# design.net
KiCad netlist of a schematic drawn in Altium Designer
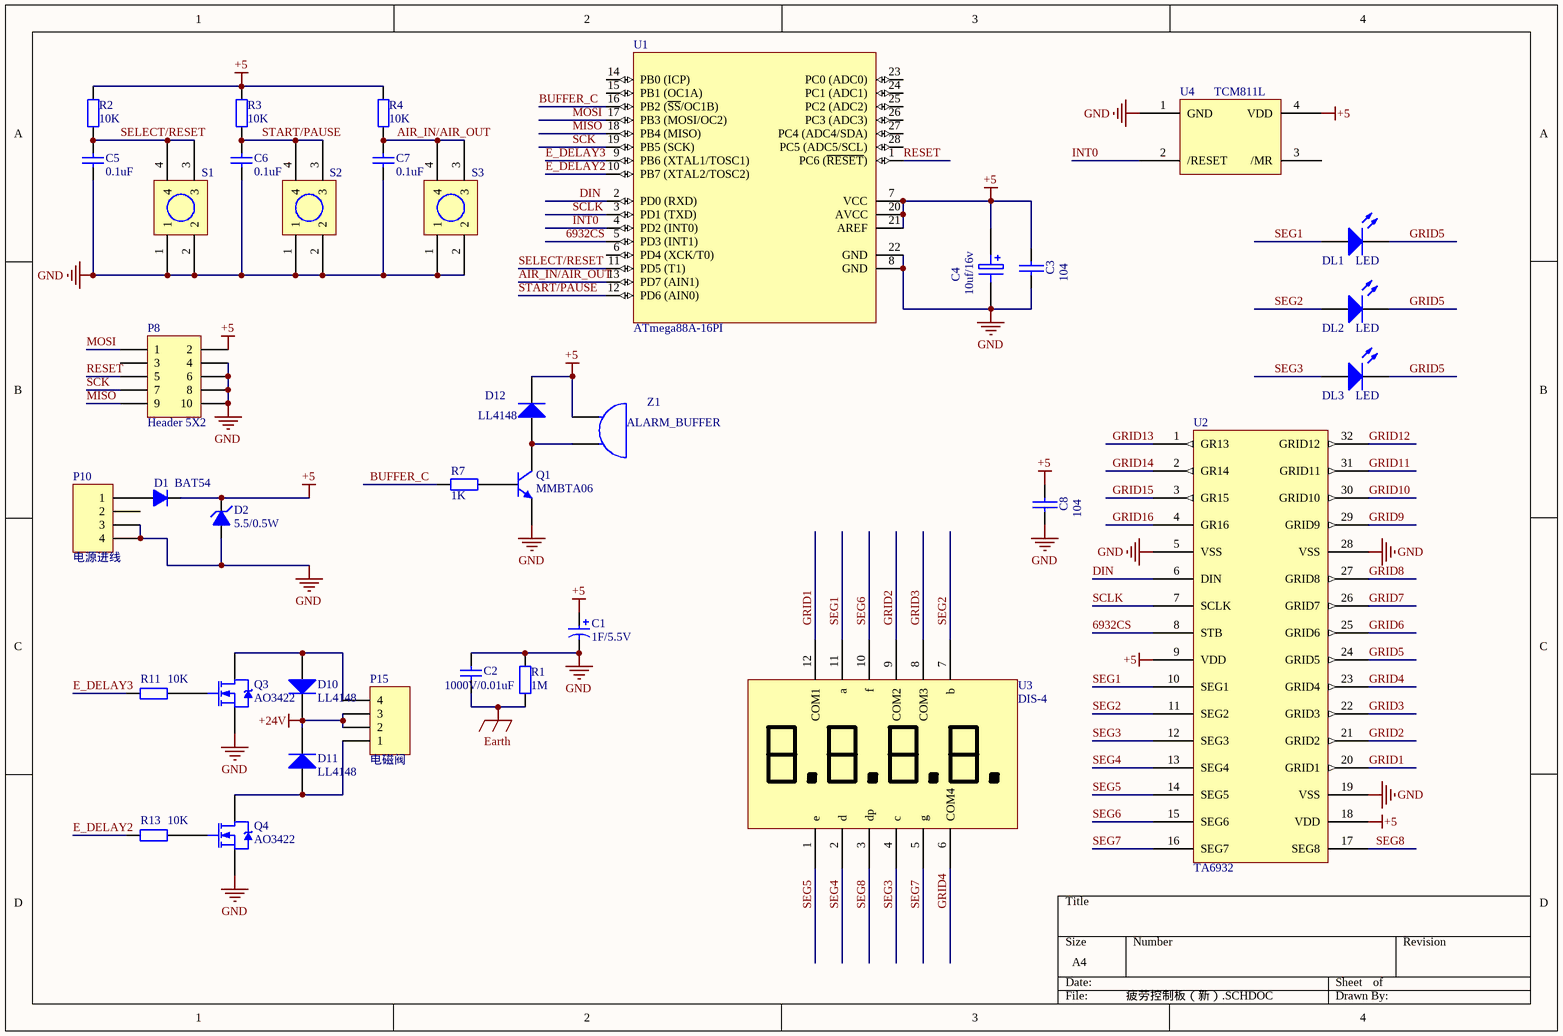
[diagram p0: 疲劳控制板（新）.SCHDOC]

(export (version "E")
  (design (tool "Eeschema 10.0.6"))
  (components
    (comp (ref "C1") (value "1F/5.5V") (footprint "法拉电容") (libsource (lib "自定义元件2") (part "电解电容")))
    (comp (ref "C2")
      (value "1000V/0.01uF")
      (footprint "0805")
      (description "Capacitor")
      (fields (field (name "Comment") "Cap") (field (name "PUBLISHER") "Altium Limited"))
      (libsource (lib "Miscellaneous Devices") (part "Cap"))
    )
    (comp (ref "C3")
      (value "104")
      (footprint "0805")
      (description "Capacitor")
      (libsource (lib "*") (part "CAP"))
    )
    (comp (ref "C4")
      (value "10uf/16v")
      (footprint "贴片极性电容(小)")
      (description "Electrolytic Capacitor")
      (libsource (lib "*") (part "ELECTRO1"))
    )
    (comp (ref "C5")
      (value "0.1uF")
      (footprint "0805")
      (description "Capacitor")
      (fields (field (name "Comment") "Cap") (field (name "PUBLISHER") "Altium Limited"))
      (libsource (lib "Miscellaneous Devices") (part "Cap"))
    )
    (comp (ref "C6")
      (value "0.1uF")
      (footprint "0805")
      (description "Capacitor")
      (fields (field (name "Comment") "Cap") (field (name "PUBLISHER") "Altium Limited"))
      (libsource (lib "Miscellaneous Devices") (part "Cap"))
    )
    (comp (ref "C7")
      (value "0.1uF")
      (footprint "0805")
      (description "Capacitor")
      (fields (field (name "Comment") "Cap") (field (name "PUBLISHER") "Altium Limited"))
      (libsource (lib "Miscellaneous Devices") (part "Cap"))
    )
    (comp (ref "C8")
      (value "104")
      (footprint "0805")
      (description "Capacitor")
      (libsource (lib "*") (part "CAP"))
    )
    (comp (ref "D1") (value "BAT54") (footprint "SOT-23") (libsource (lib "自定义元件2") (part "二极管")))
    (comp (ref "D2")
      (value "5.5/0.5W")
      (footprint "MELF-D3516-1406")
      (description "稳压二极管")
      (libsource (lib "自定义元件2") (part "稳压二极管"))
    )
    (comp (ref "D10")
      (value "LL4148")
      (footprint "MELF-D3516-1406")
      (description "Default Diode")
      (fields (field (name "PUBLISHER") "Altium Limited"))
      (libsource (lib "Miscellaneous Devices") (part "Diode"))
    )
    (comp (ref "D11")
      (value "LL4148")
      (footprint "MELF-D3516-1406")
      (description "Default Diode")
      (fields (field (name "PUBLISHER") "Altium Limited"))
      (libsource (lib "Miscellaneous Devices") (part "Diode"))
    )
    (comp (ref "D12")
      (value "LL4148")
      (footprint "MELF-D3516-1406")
      (description "Default Diode")
      (fields (field (name "PUBLISHER") "Altium Limited"))
      (libsource (lib "Miscellaneous Devices") (part "Diode"))
    )
    (comp (ref "DL1")
      (value "LED")
      (footprint "LED1")
      (description "发光二极管")
      (libsource (lib "自定义元件") (part "LED"))
    )
    (comp (ref "DL2")
      (value "LED")
      (footprint "LED1")
      (description "发光二极管")
      (libsource (lib "自定义元件") (part "LED"))
    )
    (comp (ref "DL3")
      (value "LED")
      (footprint "LED1")
      (description "发光二极管")
      (libsource (lib "自定义元件") (part "LED"))
    )
    (comp (ref "P8")
      (value "Header 5X2")
      (footprint "HDR2X5")
      (description "Header, 5-Pin, Dual row")
      (fields (field (name "PUBLISHER") "Altium Limited"))
      (libsource (lib "Miscellaneous Connectors") (part "Header 5X2"))
    )
    (comp (ref "P10")
      (value "电源进线")
      (footprint "免螺丝接线端子1")
      (description "Header, 4-Pin")
      (fields (field (name "PUBLISHER") "Altium Limited"))
      (libsource (lib "Miscellaneous Connectors") (part "MHDR1X4"))
    )
    (comp (ref "P15")
      (value "电磁阀")
      (footprint "免螺丝接线端子1")
      (description "Header, 4-Pin")
      (fields (field (name "PUBLISHER") "Altium Limited"))
      (libsource (lib "") (part "MHDR1X4_1"))
    )
    (comp (ref "Q1")
      (value "MMBTA06")
      (footprint "三极管_SOT23")
      (libsource (lib "自定义元件") (part "NPN三极管-SOT23"))
    )
    (comp (ref "Q3")
      (value "AO3422")
      (footprint "SOT-23")
      (description "N沟道功率MOSFET")
      (fields (field (name "PUBLISHER") "Altium Limited"))
      (libsource (lib "IR Discrete MOSFET - Power") (part "IRF530"))
    )
    (comp (ref "Q4")
      (value "AO3422")
      (footprint "SOT-23")
      (description "N沟道功率MOSFET")
      (fields (field (name "PUBLISHER") "Altium Limited"))
      (libsource (lib "IR Discrete MOSFET - Power") (part "IRF530"))
    )
    (comp (ref "R1")
      (value "1M")
      (footprint "0805")
      (description "Resistor")
      (fields (field (name "Comment") "Res2") (field (name "PUBLISHER") "Altium Limited"))
      (libsource (lib "") (part "Res2_1"))
    )
    (comp (ref "R2")
      (value "10K")
      (footprint "0805")
      (description "贴片电阻")
      (libsource (lib "") (part "Res2_1"))
    )
    (comp (ref "R3")
      (value "10K")
      (footprint "0805")
      (description "Resistor")
      (libsource (lib "") (part "Res2_1"))
    )
    (comp (ref "R4")
      (value "10K")
      (footprint "0805")
      (description "Resistor")
      (libsource (lib "") (part "Res2_1"))
    )
    (comp (ref "R7")
      (value "1K")
      (footprint "0805")
      (description "Resistor")
      (libsource (lib "Miscellaneous Devices") (part "Res2"))
    )
    (comp (ref "R11")
      (value "10K")
      (footprint "0805")
      (description "贴片电阻")
      (fields (field (name "PUBLISHER") "Altium Limited"))
      (libsource (lib "Miscellaneous Devices") (part "Res2"))
    )
    (comp (ref "R13")
      (value "10K")
      (footprint "0805")
      (description "贴片电阻")
      (fields (field (name "PUBLISHER") "Altium Limited"))
      (libsource (lib "Miscellaneous Devices") (part "Res2"))
    )
    (comp (ref "S1")
      (value "~")
      (footprint "AN-NIU")
      (description "S?")
      (libsource (lib "*") (part "ANJIAN"))
    )
    (comp (ref "S2")
      (value "~")
      (footprint "AN-NIU")
      (description "S?")
      (libsource (lib "*") (part "ANJIAN"))
    )
    (comp (ref "S3")
      (value "~")
      (footprint "AN-NIU")
      (description "S?")
      (libsource (lib "*") (part "ANJIAN"))
    )
    (comp (ref "U1")
      (value "ATmega88A-16PI")
      (footprint "DIP28(300mil)")
      (description "8-Bit AVR Microcontroller with 8K Bytes of In-System Programmable Flash Memory")
      (fields (field (name "PUBLISHER") "Altium Limited"))
      (libsource (lib "Atmel Microcontroller 8-Bit AVR") (part "ATmega8-16PI"))
    )
    (comp (ref "U2") (value "TA6932") (footprint "TM6932") (libsource (lib "*") (part "TM6932")))
    (comp (ref "U3") (value "DIS-4") (footprint "DIS05_4") (libsource (lib "*") (part "DIS-4")))
    (comp (ref "U4") (value "TCM811L") (footprint "SOT-143") (libsource (lib "*") (part "TCM811")))
    (comp (ref "Z1")
      (value "ALARM_BUFFER")
      (footprint "BUFFER")
      (description "Buzzer")
      (libsource (lib "*") (part "BUZZER"))
    )
  )
  (nets
    (net (code "1") (name "+5") (class "Default")
      (node (ref "C1") (pin "1") (pinfunction "1_1") (pintype "passive"))
      (node (ref "C3") (pin "1") (pinfunction "1_1") (pintype "passive"))
      (node (ref "C4") (pin "1") (pinfunction "1_1") (pintype "passive"))
      (node (ref "C8") (pin "1") (pinfunction "1_1") (pintype "passive"))
      (node (ref "D1") (pin "3") (pinfunction "3_3") (pintype "passive"))
      (node (ref "D12") (pin "2") (pinfunction "K_2") (pintype "passive"))
      (node (ref "D2") (pin "2") (pinfunction "2_2") (pintype "passive"))
      (node (ref "P8") (pin "2") (pinfunction "2_2") (pintype "passive"))
      (node (ref "R2") (pin "2") (pinfunction "2_2") (pintype "passive"))
      (node (ref "R3") (pin "2") (pinfunction "2_2") (pintype "passive"))
      (node (ref "R4") (pin "2") (pinfunction "2_2") (pintype "passive"))
      (node (ref "U1") (pin "20") (pinfunction "AVCC_20") (pintype "power_in"))
      (node (ref "U1") (pin "21") (pinfunction "AREF_21") (pintype "passive"))
      (node (ref "U1") (pin "7") (pinfunction "VCC_7") (pintype "power_in"))
      (node (ref "U2") (pin "18") (pinfunction "VDD_18") (pintype "passive"))
      (node (ref "U2") (pin "9") (pinfunction "VDD_9") (pintype "passive"))
      (node (ref "U4") (pin "4") (pinfunction "VDD_4") (pintype "power_in"))
      (node (ref "Z1") (pin "1") (pinfunction "A_1") (pintype "passive"))
    )
    (net (code "2") (name "+24V") (class "Default")
      (node (ref "D10") (pin "2") (pinfunction "K_2") (pintype "passive"))
      (node (ref "D11") (pin "2") (pinfunction "K_2") (pintype "passive"))
      (node (ref "P15") (pin "2") (pinfunction "2_2") (pintype "passive"))
      (node (ref "P15") (pin "3") (pinfunction "3_3") (pintype "passive"))
    )
    (net (code "3") (name "/6932CS") (class "Default")
      (node (ref "U1") (pin "5") (pinfunction "PD3_(INT1)_5") (pintype "bidirectional"))
      (node (ref "U2") (pin "8") (pinfunction "STB_8") (pintype "passive"))
    )
    (net (code "4") (name "/AIR_IN{slash}AIR_OUT") (class "Default")
      (node (ref "C7") (pin "2") (pinfunction "2_2") (pintype "passive"))
      (node (ref "R4") (pin "1") (pinfunction "1_1") (pintype "passive"))
      (node (ref "S3") (pin "3") (pinfunction "3_3") (pintype "passive"))
      (node (ref "S3") (pin "4") (pinfunction "4_4") (pintype "passive"))
      (node (ref "U1") (pin "13") (pinfunction "PD7_(AIN1)_13") (pintype "bidirectional"))
    )
    (net (code "5") (name "/BUFFER_C") (class "Default")
      (node (ref "R7") (pin "2") (pinfunction "2_2") (pintype "passive"))
      (node (ref "U1") (pin "16") (pinfunction "PB2_(~{SS}/OC1B)_16") (pintype "bidirectional"))
    )
    (net (code "6") (name "/DIN") (class "Default")
      (node (ref "U1") (pin "2") (pinfunction "PD0_(RXD)_2") (pintype "bidirectional"))
      (node (ref "U2") (pin "6") (pinfunction "DIN_6") (pintype "passive"))
    )
    (net (code "7") (name "/E_DELAY2") (class "Default")
      (node (ref "R13") (pin "2") (pinfunction "2_2") (pintype "passive"))
      (node (ref "U1") (pin "10") (pinfunction "PB7_(XTAL2/TOSC2)_10") (pintype "bidirectional"))
    )
    (net (code "8") (name "/E_DELAY3") (class "Default")
      (node (ref "R11") (pin "2") (pinfunction "2_2") (pintype "passive"))
      (node (ref "U1") (pin "9") (pinfunction "PB6_(XTAL1/TOSC1)_9") (pintype "bidirectional"))
    )
    (net (code "9") (name "/GRID1") (class "Default")
      (node (ref "U2") (pin "20") (pinfunction "GRID1_20") (pintype "output"))
      (node (ref "U3") (pin "12") (pinfunction "COM1_12") (pintype "passive"))
    )
    (net (code "10") (name "/GRID2") (class "Default")
      (node (ref "U2") (pin "21") (pinfunction "GRID2_21") (pintype "output"))
      (node (ref "U3") (pin "9") (pinfunction "COM2_9") (pintype "passive"))
    )
    (net (code "11") (name "/GRID3") (class "Default")
      (node (ref "U2") (pin "22") (pinfunction "GRID3_22") (pintype "output"))
      (node (ref "U3") (pin "8") (pinfunction "COM3_8") (pintype "passive"))
    )
    (net (code "12") (name "/GRID4") (class "Default")
      (node (ref "U2") (pin "23") (pinfunction "GRID4_23") (pintype "output"))
      (node (ref "U3") (pin "6") (pinfunction "COM4_6") (pintype "passive"))
    )
    (net (code "13") (name "/GRID5") (class "Default")
      (node (ref "DL1") (pin "2") (pinfunction "K_2") (pintype "passive"))
      (node (ref "DL2") (pin "2") (pinfunction "K_2") (pintype "passive"))
      (node (ref "DL3") (pin "2") (pinfunction "K_2") (pintype "passive"))
      (node (ref "U2") (pin "24") (pinfunction "GRID5_24") (pintype "output"))
    )
    (net (code "14") (name "/GRID6") (class "Default")
      (node (ref "U2") (pin "25") (pinfunction "GRID6_25") (pintype "output"))
    )
    (net (code "15") (name "/GRID7") (class "Default")
      (node (ref "U2") (pin "26") (pinfunction "GRID7_26") (pintype "output"))
    )
    (net (code "16") (name "/GRID8") (class "Default")
      (node (ref "U2") (pin "27") (pinfunction "GRID8_27") (pintype "output"))
    )
    (net (code "17") (name "/GRID9") (class "Default")
      (node (ref "U2") (pin "29") (pinfunction "GRID9_29") (pintype "output"))
    )
    (net (code "18") (name "/GRID10") (class "Default")
      (node (ref "U2") (pin "30") (pinfunction "GRID10_30") (pintype "output"))
    )
    (net (code "19") (name "/GRID11") (class "Default")
      (node (ref "U2") (pin "31") (pinfunction "GRID11_31") (pintype "output"))
    )
    (net (code "20") (name "/GRID12") (class "Default")
      (node (ref "U2") (pin "32") (pinfunction "GRID12_32") (pintype "output"))
    )
    (net (code "21") (name "/GRID13") (class "Default")
      (node (ref "U2") (pin "1") (pinfunction "GR13_1") (pintype "output"))
    )
    (net (code "22") (name "/GRID14") (class "Default")
      (node (ref "U2") (pin "2") (pinfunction "GR14_2") (pintype "output"))
    )
    (net (code "23") (name "/GRID15") (class "Default")
      (node (ref "U2") (pin "3") (pinfunction "GR15_3") (pintype "output"))
    )
    (net (code "24") (name "/GRID16") (class "Default")
      (node (ref "U2") (pin "4") (pinfunction "GR16_4") (pintype "passive"))
    )
    (net (code "25") (name "/INT0") (class "Default")
      (node (ref "U1") (pin "4") (pinfunction "PD2_(INT0)_4") (pintype "bidirectional"))
      (node (ref "U4") (pin "2") (pinfunction "/RESET_2") (pintype "power_in"))
    )
    (net (code "26") (name "/MISO") (class "Default")
      (node (ref "P8") (pin "9") (pinfunction "9_9") (pintype "passive"))
      (node (ref "U1") (pin "18") (pinfunction "PB4_(MISO)_18") (pintype "bidirectional"))
    )
    (net (code "27") (name "/MOSI") (class "Default")
      (node (ref "P8") (pin "1") (pinfunction "1_1") (pintype "passive"))
      (node (ref "U1") (pin "17") (pinfunction "PB3_(MOSI/OC2)_17") (pintype "bidirectional"))
    )
    (net (code "28") (name "/RESET") (class "Default")
      (node (ref "P8") (pin "5") (pinfunction "5_5") (pintype "passive"))
      (node (ref "U1") (pin "1") (pinfunction "PC6_(~{RESET})_1") (pintype "bidirectional"))
    )
    (net (code "29") (name "/SCK") (class "Default")
      (node (ref "P8") (pin "7") (pinfunction "7_7") (pintype "passive"))
      (node (ref "U1") (pin "19") (pinfunction "PB5_(SCK)_19") (pintype "bidirectional"))
    )
    (net (code "30") (name "/SCLK") (class "Default")
      (node (ref "U1") (pin "3") (pinfunction "PD1_(TXD)_3") (pintype "bidirectional"))
      (node (ref "U2") (pin "7") (pinfunction "SCLK_7") (pintype "passive"))
    )
    (net (code "31") (name "/SEG1") (class "Default")
      (node (ref "DL1") (pin "1") (pinfunction "A_1") (pintype "passive"))
      (node (ref "U2") (pin "10") (pinfunction "SEG1_10") (pintype "passive"))
      (node (ref "U3") (pin "11") (pinfunction "a_11") (pintype "passive"))
    )
    (net (code "32") (name "/SEG2") (class "Default")
      (node (ref "DL2") (pin "1") (pinfunction "A_1") (pintype "passive"))
      (node (ref "U2") (pin "11") (pinfunction "SEG2_11") (pintype "passive"))
      (node (ref "U3") (pin "7") (pinfunction "b_7") (pintype "passive"))
    )
    (net (code "33") (name "/SEG3") (class "Default")
      (node (ref "DL3") (pin "1") (pinfunction "A_1") (pintype "passive"))
      (node (ref "U2") (pin "12") (pinfunction "SEG3_12") (pintype "passive"))
      (node (ref "U3") (pin "4") (pinfunction "c_4") (pintype "passive"))
    )
    (net (code "34") (name "/SEG4") (class "Default")
      (node (ref "U2") (pin "13") (pinfunction "SEG4_13") (pintype "passive"))
      (node (ref "U3") (pin "2") (pinfunction "d_2") (pintype "passive"))
    )
    (net (code "35") (name "/SEG5") (class "Default")
      (node (ref "U2") (pin "14") (pinfunction "SEG5_14") (pintype "passive"))
      (node (ref "U3") (pin "1") (pinfunction "e_1") (pintype "passive"))
    )
    (net (code "36") (name "/SEG6") (class "Default")
      (node (ref "U2") (pin "15") (pinfunction "SEG6_15") (pintype "passive"))
      (node (ref "U3") (pin "10") (pinfunction "f_10") (pintype "passive"))
    )
    (net (code "37") (name "/SEG7") (class "Default")
      (node (ref "U2") (pin "16") (pinfunction "SEG7_16") (pintype "passive"))
      (node (ref "U3") (pin "5") (pinfunction "g_5") (pintype "passive"))
    )
    (net (code "38") (name "/SEG8") (class "Default")
      (node (ref "U2") (pin "17") (pinfunction "SEG8_17") (pintype "passive"))
      (node (ref "U3") (pin "3") (pinfunction "dp_3") (pintype "passive"))
    )
    (net (code "39") (name "/SELECT{slash}RESET") (class "Default")
      (node (ref "C5") (pin "2") (pinfunction "2_2") (pintype "passive"))
      (node (ref "R2") (pin "1") (pinfunction "1_1") (pintype "passive"))
      (node (ref "S1") (pin "3") (pinfunction "3_3") (pintype "passive"))
      (node (ref "S1") (pin "4") (pinfunction "4_4") (pintype "passive"))
      (node (ref "U1") (pin "11") (pinfunction "PD5_(T1)_11") (pintype "bidirectional"))
    )
    (net (code "40") (name "/START{slash}PAUSE") (class "Default")
      (node (ref "C6") (pin "2") (pinfunction "2_2") (pintype "passive"))
      (node (ref "R3") (pin "1") (pinfunction "1_1") (pintype "passive"))
      (node (ref "S2") (pin "3") (pinfunction "3_3") (pintype "passive"))
      (node (ref "S2") (pin "4") (pinfunction "4_4") (pintype "passive"))
      (node (ref "U1") (pin "12") (pinfunction "PD6_(AIN0)_12") (pintype "bidirectional"))
    )
    (net (code "41") (name "Earth") (class "Default")
      (node (ref "C2") (pin "1") (pinfunction "1_1") (pintype "passive"))
      (node (ref "R1") (pin "1") (pinfunction "1_1") (pintype "passive"))
    )
    (net (code "42") (name "GND") (class "Default")
      (node (ref "C1") (pin "2") (pinfunction "2_2") (pintype "passive"))
      (node (ref "C2") (pin "2") (pinfunction "2_2") (pintype "passive"))
      (node (ref "C3") (pin "2") (pinfunction "2_2") (pintype "passive"))
      (node (ref "C4") (pin "2") (pinfunction "2_2") (pintype "passive"))
      (node (ref "C5") (pin "1") (pinfunction "1_1") (pintype "passive"))
      (node (ref "C6") (pin "1") (pinfunction "1_1") (pintype "passive"))
      (node (ref "C7") (pin "1") (pinfunction "1_1") (pintype "passive"))
      (node (ref "C8") (pin "2") (pinfunction "2_2") (pintype "passive"))
      (node (ref "D2") (pin "1") (pinfunction "1_1") (pintype "passive"))
      (node (ref "P10") (pin "3") (pinfunction "3_3") (pintype "passive"))
      (node (ref "P10") (pin "4") (pinfunction "4_4") (pintype "passive"))
      (node (ref "P8") (pin "10") (pinfunction "10_10") (pintype "passive"))
      (node (ref "P8") (pin "4") (pinfunction "4_4") (pintype "passive"))
      (node (ref "P8") (pin "6") (pinfunction "6_6") (pintype "passive"))
      (node (ref "P8") (pin "8") (pinfunction "8_8") (pintype "passive"))
      (node (ref "Q1") (pin "E") (pinfunction "E_E") (pintype "passive"))
      (node (ref "Q3") (pin "3") (pinfunction "S_3") (pintype "passive"))
      (node (ref "Q4") (pin "3") (pinfunction "S_3") (pintype "passive"))
      (node (ref "R1") (pin "2") (pinfunction "2_2") (pintype "passive"))
      (node (ref "S1") (pin "1") (pinfunction "1_1") (pintype "passive"))
      (node (ref "S1") (pin "2") (pinfunction "2_2") (pintype "passive"))
      (node (ref "S2") (pin "1") (pinfunction "1_1") (pintype "passive"))
      (node (ref "S2") (pin "2") (pinfunction "2_2") (pintype "passive"))
      (node (ref "S3") (pin "1") (pinfunction "1_1") (pintype "passive"))
      (node (ref "S3") (pin "2") (pinfunction "2_2") (pintype "passive"))
      (node (ref "U1") (pin "22") (pinfunction "GND_22") (pintype "power_in"))
      (node (ref "U1") (pin "8") (pinfunction "GND_8") (pintype "power_in"))
      (node (ref "U2") (pin "19") (pinfunction "VSS_19") (pintype "passive"))
      (node (ref "U2") (pin "28") (pinfunction "VSS_28") (pintype "passive"))
      (node (ref "U2") (pin "5") (pinfunction "VSS_5") (pintype "passive"))
      (node (ref "U4") (pin "1") (pinfunction "GND_1") (pintype "power_in"))
    )
    (net (code "43") (name "Net-(D1-Pad1)") (class "Default")
      (node (ref "D1") (pin "1") (pinfunction "1_1") (pintype "passive"))
      (node (ref "P10") (pin "1") (pinfunction "1_1") (pintype "passive"))
    )
    (net (code "44") (name "Net-(D10-A)") (class "Default")
      (node (ref "D10") (pin "1") (pinfunction "A_1") (pintype "passive"))
      (node (ref "P15") (pin "4") (pinfunction "4_4") (pintype "passive"))
      (node (ref "Q3") (pin "2") (pinfunction "D_2") (pintype "passive"))
    )
    (net (code "45") (name "Net-(D11-A)") (class "Default")
      (node (ref "D11") (pin "1") (pinfunction "A_1") (pintype "passive"))
      (node (ref "P15") (pin "1") (pinfunction "1_1") (pintype "passive"))
      (node (ref "Q4") (pin "2") (pinfunction "D_2") (pintype "passive"))
    )
    (net (code "46") (name "Net-(D12-A)") (class "Default")
      (node (ref "D12") (pin "1") (pinfunction "A_1") (pintype "passive"))
      (node (ref "Q1") (pin "C") (pinfunction "C_C") (pintype "passive"))
      (node (ref "Z1") (pin "2") (pinfunction "B_2") (pintype "passive"))
    )
    (net (code "47") (name "Net-(Q1-PadB)") (class "Default")
      (node (ref "Q1") (pin "B") (pinfunction "B_B") (pintype "passive"))
      (node (ref "R7") (pin "1") (pinfunction "1_1") (pintype "passive"))
    )
    (net (code "48") (name "Net-(Q3-G)") (class "Default")
      (node (ref "Q3") (pin "1") (pinfunction "G_1") (pintype "passive"))
      (node (ref "R11") (pin "1") (pinfunction "1_1") (pintype "passive"))
    )
    (net (code "49") (name "Net-(Q4-G)") (class "Default")
      (node (ref "Q4") (pin "1") (pinfunction "G_1") (pintype "passive"))
      (node (ref "R13") (pin "1") (pinfunction "1_1") (pintype "passive"))
    )
    (net (code "50") (name "unconnected-(P8-Pad3)") (class "Default")
      (node (ref "P8") (pin "3") (pinfunction "3_3") (pintype "passive"))
    )
    (net (code "51") (name "unconnected-(P10-Pad2)") (class "Default")
      (node (ref "P10") (pin "2") (pinfunction "2_2") (pintype "passive"))
    )
    (net (code "52") (name "unconnected-(U1-PB0_(ICP)-Pad14)") (class "Default")
      (node (ref "U1") (pin "14") (pinfunction "PB0_(ICP)_14") (pintype "bidirectional"))
    )
    (net (code "53") (name "unconnected-(U1-PB1_(OC1A)-Pad15)") (class "Default")
      (node (ref "U1") (pin "15") (pinfunction "PB1_(OC1A)_15") (pintype "bidirectional"))
    )
    (net (code "54") (name "unconnected-(U1-PC0_(ADC0)-Pad23)") (class "Default")
      (node (ref "U1") (pin "23") (pinfunction "PC0_(ADC0)_23") (pintype "bidirectional"))
    )
    (net (code "55") (name "unconnected-(U1-PC1_(ADC1)-Pad24)") (class "Default")
      (node (ref "U1") (pin "24") (pinfunction "PC1_(ADC1)_24") (pintype "bidirectional"))
    )
    (net (code "56") (name "unconnected-(U1-PC2_(ADC2)-Pad25)") (class "Default")
      (node (ref "U1") (pin "25") (pinfunction "PC2_(ADC2)_25") (pintype "bidirectional"))
    )
    (net (code "57") (name "unconnected-(U1-PC3_(ADC3)-Pad26)") (class "Default")
      (node (ref "U1") (pin "26") (pinfunction "PC3_(ADC3)_26") (pintype "bidirectional"))
    )
    (net (code "58") (name "unconnected-(U1-PC4_(ADC4{slash}SDA)-Pad27)") (class "Default")
      (node (ref "U1") (pin "27") (pinfunction "PC4_(ADC4/SDA)_27") (pintype "bidirectional"))
    )
    (net (code "59") (name "unconnected-(U1-PC5_(ADC5{slash}SCL)-Pad28)") (class "Default")
      (node (ref "U1") (pin "28") (pinfunction "PC5_(ADC5/SCL)_28") (pintype "bidirectional"))
    )
    (net (code "60") (name "unconnected-(U1-PD4_(XCK{slash}T0)-Pad6)") (class "Default")
      (node (ref "U1") (pin "6") (pinfunction "PD4_(XCK/T0)_6") (pintype "bidirectional"))
    )
    (net (code "61") (name "unconnected-(U4-{slash}MR-Pad3)") (class "Default")
      (node (ref "U4") (pin "3") (pinfunction "/MR_3") (pintype "power_in"))
    )
  )
)
